# mcu.net
KiCad netlist of a schematic drawn in Altium Designer
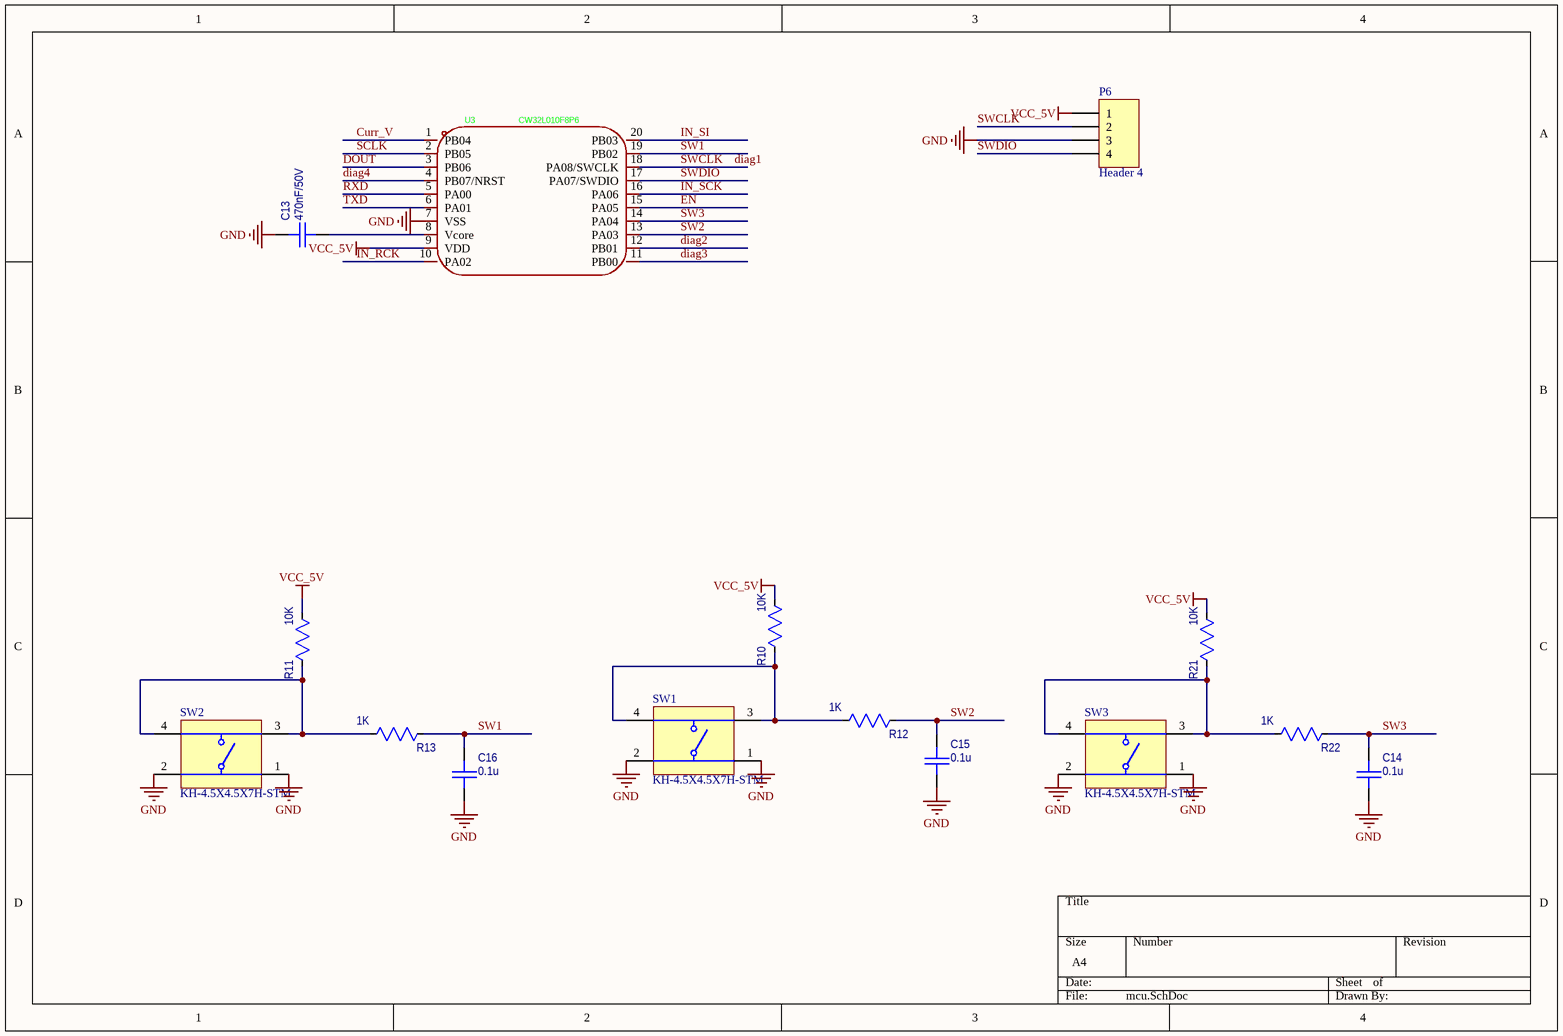
[diagram p0: mcu.SchDoc]

(export (version "E")
  (design (tool "Eeschema 10.0.6"))
  (components
    (comp (ref "C13")
      (value "470nF/50V")
      (footprint "CAPC1608X092N_0603")
      (description "Capacitor, MLCC")
      (fields (field (name "MANUFACTURER") "KEMET") (field (name "PARTNUMBER") "C0603C104M5RACTU"))
      (libsource (lib "Karl") (part "Capacitor_0603"))
    )
    (comp (ref "C14")
      (value "0.1u")
      (footprint "CAPC1608X092N_0603")
      (description "Capacitor, MLCC")
      (fields (field (name "MANUFACTURER") "KEMET") (field (name "PARTNUMBER") "C0603C104M5RACTU"))
      (libsource (lib "Karl") (part "Capacitor_0603"))
    )
    (comp (ref "C15")
      (value "0.1u")
      (footprint "CAPC1608X092N_0603")
      (description "Capacitor, MLCC")
      (fields (field (name "MANUFACTURER") "KEMET") (field (name "PARTNUMBER") "C0603C104M5RACTU"))
      (libsource (lib "Karl") (part "Capacitor_0603"))
    )
    (comp (ref "C16")
      (value "0.1u")
      (footprint "CAPC1608X092N_0603")
      (description "Capacitor, MLCC")
      (fields (field (name "MANUFACTURER") "KEMET") (field (name "PARTNUMBER") "C0603C104M5RACTU"))
      (libsource (lib "Karl") (part "Capacitor_0603"))
    )
    (comp (ref "P6")
      (value "Header 4")
      (footprint "1.27-4P")
      (fields (field (name "PUBLISHER") "Altium Limited"))
      (libsource (lib "Miscellaneous Connectors") (part "Header 4"))
    )
    (comp (ref "R10")
      (value "10K")
      (footprint "RESC1608X055N_0603")
      (description "Resistor, Standard")
      (fields (field (name "MANUFACTURER") "Yageo") (field (name "PARTNUMBER") "RC0603FR-1075KL"))
      (libsource (lib "Karl") (part "Resistor_0603"))
    )
    (comp (ref "R11")
      (value "10K")
      (footprint "RESC1608X055N_0603")
      (description "Resistor, Standard")
      (fields (field (name "MANUFACTURER") "Yageo") (field (name "PARTNUMBER") "RC0603FR-1075KL"))
      (libsource (lib "Karl") (part "Resistor_0603"))
    )
    (comp (ref "R12")
      (value "1K")
      (footprint "RESC1608X055N_0603")
      (description "Resistor, Standard")
      (fields (field (name "MANUFACTURER") "Yageo") (field (name "PARTNUMBER") "RC0603FR-1075KL"))
      (libsource (lib "Karl") (part "Resistor_0603"))
    )
    (comp (ref "R13")
      (value "1K")
      (footprint "RESC1608X055N_0603")
      (description "Resistor, Standard")
      (fields (field (name "MANUFACTURER") "Yageo") (field (name "PARTNUMBER") "RC0603FR-1075KL"))
      (libsource (lib "Karl") (part "Resistor_0603"))
    )
    (comp (ref "R21")
      (value "10K")
      (footprint "RESC1608X055N_0603")
      (description "Resistor, Standard")
      (fields (field (name "MANUFACTURER") "Yageo") (field (name "PARTNUMBER") "RC0603FR-1075KL"))
      (libsource (lib "Karl") (part "Resistor_0603"))
    )
    (comp (ref "R22")
      (value "1K")
      (footprint "RESC1608X055N_0603")
      (description "Resistor, Standard")
      (fields (field (name "MANUFACTURER") "Yageo") (field (name "PARTNUMBER") "RC0603FR-1075KL"))
      (libsource (lib "Karl") (part "Resistor_0603"))
    )
    (comp (ref "SW1")
      (value "KH-4.5X4.5X7H-STM")
      (footprint "SW-SMD_4P-L4.5-W4.5-P3.00-LS6.8:SW-SMD_4P-L4.5-W4.5-P3.00-LS6.8")
      (description "Tactile Switch, 6 × 6 mm, Height 5.0mm, 4-Pin THD")
      (fields (field (name "PARTNUMBER") "J1L0503110"))
      (libsource (lib "Bogen") (part "J1L0503110"))
    )
    (comp (ref "SW2")
      (value "KH-4.5X4.5X7H-STM")
      (footprint "SW-SMD_4P-L4.5-W4.5-P3.00-LS6.8:SW-SMD_4P-L4.5-W4.5-P3.00-LS6.8")
      (description "Tactile Switch, 6 × 6 mm, Height 5.0mm, 4-Pin THD")
      (fields (field (name "PARTNUMBER") "J1L0503110"))
      (libsource (lib "Bogen") (part "J1L0503110"))
    )
    (comp (ref "SW3")
      (value "KH-4.5X4.5X7H-STM")
      (footprint "SW-SMD_4P-L4.5-W4.5-P3.00-LS6.8:SW-SMD_4P-L4.5-W4.5-P3.00-LS6.8")
      (description "Tactile Switch, 6 × 6 mm, Height 5.0mm, 4-Pin THD")
      (fields (field (name "PARTNUMBER") "J1L0503110"))
      (libsource (lib "Bogen") (part "J1L0503110"))
    )
    (comp (ref "U3")
      (value "CW32L010F8P6")
      (footprint "TSSOP-20_L6.5-W4.4-P0.65-LS6.4-BL:TSSOP-20_L6.5-W4.4-P0.65-LS6.4-BL")
      (fields (field (name "MANUFACTURER") "CW(芯源)"))
      (libsource (lib "altium-import") (part "root_0_CW32L010F8P6_"))
    )
  )
  (nets
    (net (code "1") (name "/Curr_V") (class "Default")
      (node (ref "U3") (pin "1") (pinfunction "PB04_1") (pintype "passive"))
    )
    (net (code "2") (name "/DOUT") (class "Default")
      (node (ref "U3") (pin "3") (pinfunction "PB06_3") (pintype "passive"))
    )
    (net (code "3") (name "/EN") (class "Default")
      (node (ref "U3") (pin "15") (pinfunction "PA05_15") (pintype "passive"))
    )
    (net (code "4") (name "/IN_RCK") (class "Default")
      (node (ref "U3") (pin "10") (pinfunction "PA02_10") (pintype "passive"))
    )
    (net (code "5") (name "/IN_SCK") (class "Default")
      (node (ref "U3") (pin "16") (pinfunction "PA06_16") (pintype "passive"))
    )
    (net (code "6") (name "/IN_SI") (class "Default")
      (node (ref "U3") (pin "20") (pinfunction "PB03_20") (pintype "passive"))
    )
    (net (code "7") (name "/RXD") (class "Default")
      (node (ref "U3") (pin "5") (pinfunction "PA00_5") (pintype "passive"))
    )
    (net (code "8") (name "/SCLK") (class "Default")
      (node (ref "U3") (pin "2") (pinfunction "PB05_2") (pintype "passive"))
    )
    (net (code "9") (name "/SW1") (class "Default")
      (node (ref "C16") (pin "1") (pinfunction "1_1") (pintype "passive"))
      (node (ref "R13") (pin "2") (pinfunction "2_2") (pintype "passive"))
      (node (ref "U3") (pin "19") (pinfunction "PB02_19") (pintype "passive"))
    )
    (net (code "10") (name "/SW2") (class "Default")
      (node (ref "C15") (pin "1") (pinfunction "1_1") (pintype "passive"))
      (node (ref "R12") (pin "2") (pinfunction "2_2") (pintype "passive"))
      (node (ref "U3") (pin "13") (pinfunction "PA03_13") (pintype "passive"))
    )
    (net (code "11") (name "/SW3") (class "Default")
      (node (ref "C14") (pin "1") (pinfunction "1_1") (pintype "passive"))
      (node (ref "R22") (pin "2") (pinfunction "2_2") (pintype "passive"))
      (node (ref "U3") (pin "14") (pinfunction "PA04_14") (pintype "passive"))
    )
    (net (code "12") (name "/SWCLK") (class "Default")
      (node (ref "P6") (pin "2") (pinfunction "2_2") (pintype "passive"))
      (node (ref "U3") (pin "18") (pinfunction "PA08/SWCLK_18") (pintype "passive"))
    )
    (net (code "13") (name "/SWDIO") (class "Default")
      (node (ref "P6") (pin "4") (pinfunction "4_4") (pintype "passive"))
      (node (ref "U3") (pin "17") (pinfunction "PA07/SWDIO_17") (pintype "passive"))
    )
    (net (code "14") (name "/TXD") (class "Default")
      (node (ref "U3") (pin "6") (pinfunction "PA01_6") (pintype "passive"))
    )
    (net (code "15") (name "/diag2") (class "Default")
      (node (ref "U3") (pin "12") (pinfunction "PB01_12") (pintype "passive"))
    )
    (net (code "16") (name "/diag3") (class "Default")
      (node (ref "U3") (pin "11") (pinfunction "PB00_11") (pintype "passive"))
    )
    (net (code "17") (name "/diag4") (class "Default")
      (node (ref "U3") (pin "4") (pinfunction "PB07/NRST_4") (pintype "passive"))
    )
    (net (code "18") (name "GND") (class "Default")
      (node (ref "C13") (pin "1") (pinfunction "1_1") (pintype "passive"))
      (node (ref "C14") (pin "2") (pinfunction "2_2") (pintype "passive"))
      (node (ref "C15") (pin "2") (pinfunction "2_2") (pintype "passive"))
      (node (ref "C16") (pin "2") (pinfunction "2_2") (pintype "passive"))
      (node (ref "P6") (pin "3") (pinfunction "3_3") (pintype "passive"))
      (node (ref "SW1") (pin "1") (pinfunction "1_1") (pintype "passive"))
      (node (ref "SW1") (pin "2") (pinfunction "2_2") (pintype "passive"))
      (node (ref "SW2") (pin "1") (pinfunction "1_1") (pintype "passive"))
      (node (ref "SW2") (pin "2") (pinfunction "2_2") (pintype "passive"))
      (node (ref "SW3") (pin "1") (pinfunction "1_1") (pintype "passive"))
      (node (ref "SW3") (pin "2") (pinfunction "2_2") (pintype "passive"))
      (node (ref "U3") (pin "7") (pinfunction "VSS_7") (pintype "passive"))
    )
    (net (code "19") (name "Net-(R10-Pad2)") (class "Default")
      (node (ref "R10") (pin "2") (pinfunction "2_2") (pintype "passive"))
      (node (ref "R12") (pin "1") (pinfunction "1_1") (pintype "passive"))
      (node (ref "SW1") (pin "3") (pinfunction "3_3") (pintype "passive"))
      (node (ref "SW1") (pin "4") (pinfunction "4_4") (pintype "passive"))
    )
    (net (code "20") (name "Net-(R11-Pad2)") (class "Default")
      (node (ref "R11") (pin "2") (pinfunction "2_2") (pintype "passive"))
      (node (ref "R13") (pin "1") (pinfunction "1_1") (pintype "passive"))
      (node (ref "SW2") (pin "3") (pinfunction "3_3") (pintype "passive"))
      (node (ref "SW2") (pin "4") (pinfunction "4_4") (pintype "passive"))
    )
    (net (code "21") (name "Net-(R21-Pad2)") (class "Default")
      (node (ref "R21") (pin "2") (pinfunction "2_2") (pintype "passive"))
      (node (ref "R22") (pin "1") (pinfunction "1_1") (pintype "passive"))
      (node (ref "SW3") (pin "3") (pinfunction "3_3") (pintype "passive"))
      (node (ref "SW3") (pin "4") (pinfunction "4_4") (pintype "passive"))
    )
    (net (code "22") (name "Net-(U3-Vcore)") (class "Default")
      (node (ref "C13") (pin "2") (pinfunction "2_2") (pintype "passive"))
      (node (ref "U3") (pin "8") (pinfunction "Vcore_8") (pintype "passive"))
    )
    (net (code "23") (name "VCC_5V") (class "Default")
      (node (ref "P6") (pin "1") (pinfunction "1_1") (pintype "passive"))
      (node (ref "R10") (pin "1") (pinfunction "1_1") (pintype "passive"))
      (node (ref "R11") (pin "1") (pinfunction "1_1") (pintype "passive"))
      (node (ref "R21") (pin "1") (pinfunction "1_1") (pintype "passive"))
      (node (ref "U3") (pin "9") (pinfunction "VDD_9") (pintype "passive"))
    )
  )
)
